# lora-slim.net
KiCad netlist of a schematic drawn in EAGLE
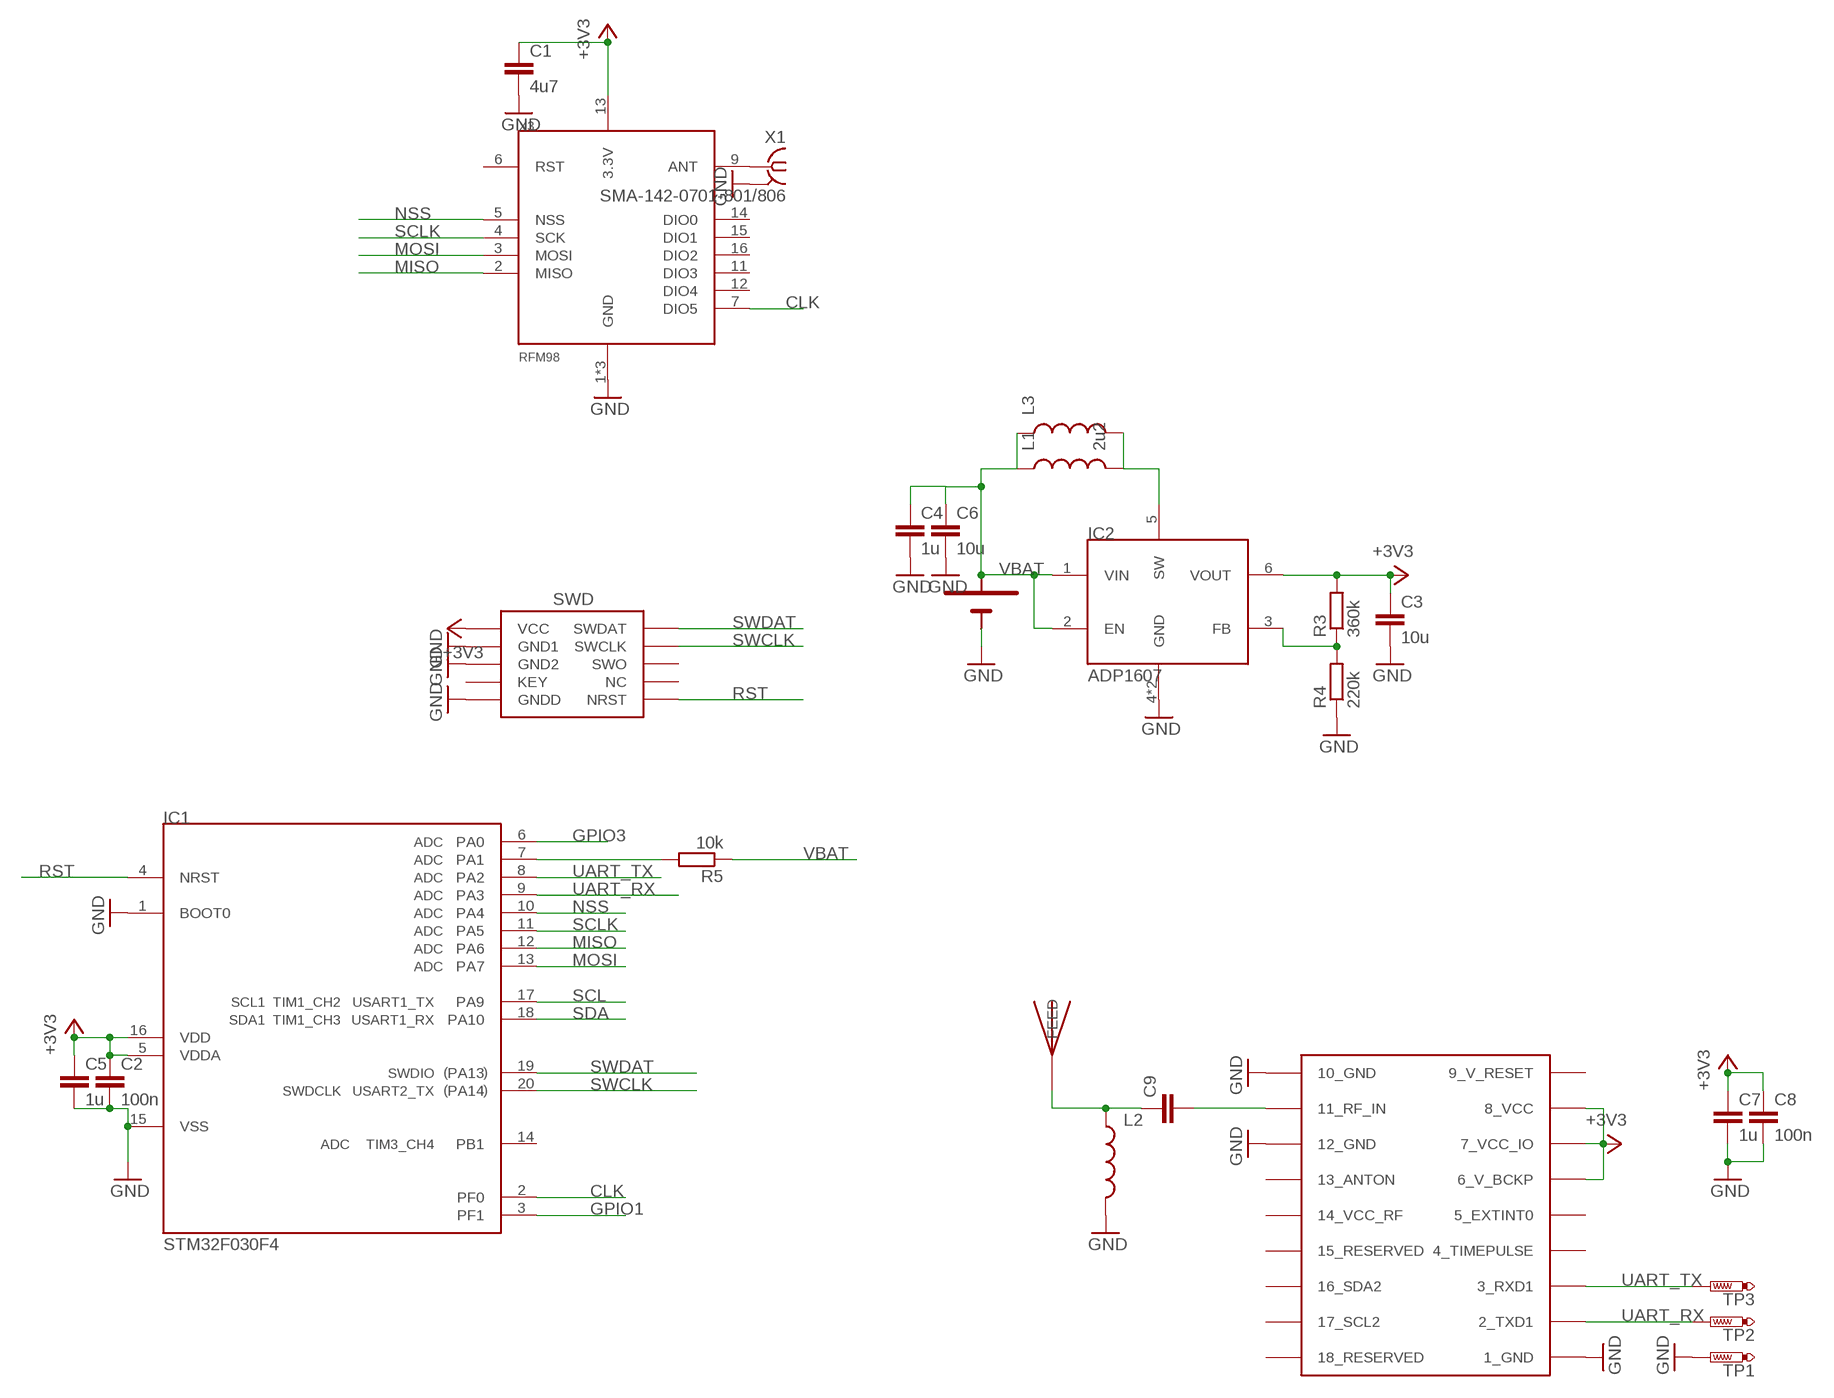
[diagram p0: schematic, sheet 1]

(export (version "E")
  (design (tool "Eeschema 10.0.6"))
  (components
    (comp (ref "C1")
      (value "4u7")
      (footprint "eagle-import:C0603")
      (libsource (lib "eagle-import") (part "C-EUC0603"))
    )
    (comp (ref "C2")
      (value "100n")
      (footprint "eagle-import:C0603")
      (libsource (lib "eagle-import") (part "C-EUC0603"))
    )
    (comp (ref "C3")
      (value "10u")
      (footprint "eagle-import:C0805")
      (libsource (lib "eagle-import") (part "C-EUC0805"))
    )
    (comp (ref "C4")
      (value "1u")
      (footprint "eagle-import:C0603")
      (libsource (lib "eagle-import") (part "C-EUC0603"))
    )
    (comp (ref "C5")
      (value "1u")
      (footprint "eagle-import:C0603")
      (libsource (lib "eagle-import") (part "C-EUC0603"))
    )
    (comp (ref "C6")
      (value "10u")
      (footprint "eagle-import:C0805")
      (libsource (lib "eagle-import") (part "C-EUC0805"))
    )
    (comp (ref "C7")
      (value "1u")
      (footprint "eagle-import:C0603")
      (libsource (lib "eagle-import") (part "C-EUC0603"))
    )
    (comp (ref "C8")
      (value "100n")
      (footprint "eagle-import:C0603")
      (libsource (lib "eagle-import") (part "C-EUC0603"))
    )
    (comp (ref "C9")
      (value "C-EUC0603")
      (footprint "eagle-import:C0603")
      (libsource (lib "eagle-import") (part "C-EUC0603"))
    )
    (comp (ref "IC1")
      (value "STM32F030F4")
      (footprint "eagle-import:TSSOP20")
      (libsource (lib "eagle-import") (part "STM32F030F4"))
    )
    (comp (ref "IC2")
      (value "ADP1607")
      (footprint "eagle-import:LFCSP6")
      (libsource (lib "eagle-import") (part "ADP1607"))
    )
    (comp (ref "J1")
      (value "SWD_PTH_SHROUD")
      (footprint "eagle-import:SWD_PTH_SHROUD")
      (libsource (lib "eagle-import") (part "SWD_PTH_SHROUD"))
    )
    (comp (ref "L1")
      (value "2u2")
      (footprint "eagle-import:0805")
      (libsource (lib "eagle-import") (part "INDUCTOR0805"))
    )
    (comp (ref "L2")
      (value "INDUCTOR0603")
      (footprint "eagle-import:0603")
      (libsource (lib "eagle-import") (part "INDUCTOR0603"))
    )
    (comp (ref "L3")
      (value "INDUCTOR1210")
      (footprint "eagle-import:1210")
      (libsource (lib "eagle-import") (part "INDUCTOR1210"))
    )
    (comp (ref "R3")
      (value "360k")
      (footprint "eagle-import:R0603")
      (libsource (lib "eagle-import") (part "R-EU_R0603"))
    )
    (comp (ref "R4")
      (value "220k")
      (footprint "eagle-import:R0603")
      (libsource (lib "eagle-import") (part "R-EU_R0603"))
    )
    (comp (ref "R5")
      (value "10k")
      (footprint "eagle-import:R0603")
      (libsource (lib "eagle-import") (part "R-EU_R0603"))
    )
    (comp (ref "TP1")
      (value "PTR1B1,27")
      (footprint "eagle-import:B1,27")
      (libsource (lib "eagle-import") (part "PTR1B1,27"))
    )
    (comp (ref "TP2")
      (value "PTR1B1,27")
      (footprint "eagle-import:B1,27")
      (libsource (lib "eagle-import") (part "PTR1B1,27"))
    )
    (comp (ref "TP3")
      (value "PTR1B1,27")
      (footprint "eagle-import:B1,27")
      (libsource (lib "eagle-import") (part "PTR1B1,27"))
    )
    (comp (ref "U$5")
      (value "JTI_ANTENNA-1575AT43A40")
      (footprint "eagle-import:JTI_ANTENNA-1575AT43A40")
      (libsource (lib "eagle-import") (part "JTI_ANTENNA-1575AT43A40"))
    )
    (comp (ref "U$6")
      (value "KEYSTONE-53")
      (footprint "eagle-import:KEYSTONE53")
      (libsource (lib "eagle-import") (part "KEYSTONE-53"))
    )
    (comp (ref "X1")
      (value "SMA-142-0701-801/806")
      (footprint "eagle-import:J502-ND-142-0701-801_806")
      (fields (field (name "MF") "JOHNSON COMPONENTS") (field (name "MPN") "142-0701-801"))
      (libsource (lib "eagle-import") (part "SMA-142-0701-801/806"))
    )
    (comp (ref "X2")
      (value "UBLOX_MAX")
      (footprint "eagle-import:UBLOX_MAX")
      (libsource (lib "eagle-import") (part "UBLOX_MAX"))
    )
    (comp (ref "X3")
      (value "RFM98")
      (footprint "eagle-import:RFM97")
      (libsource (lib "eagle-import") (part "RFM98"))
    )
  )
  (nets
    (net (code "1") (name "+3V3") (class "Default")
      (node (ref "C1") (pin "1") (pinfunction "1_1") (pintype "passive"))
      (node (ref "C2") (pin "1") (pinfunction "1_1") (pintype "passive"))
      (node (ref "C3") (pin "1") (pinfunction "1_1") (pintype "passive"))
      (node (ref "C5") (pin "1") (pinfunction "1_1") (pintype "passive"))
      (node (ref "C7") (pin "1") (pinfunction "1_1") (pintype "passive"))
      (node (ref "C8") (pin "1") (pinfunction "1_1") (pintype "passive"))
      (node (ref "IC1") (pin "16") (pinfunction "VDD_16") (pintype "power_in"))
      (node (ref "IC1") (pin "5") (pinfunction "VDDA_5") (pintype "power_in"))
      (node (ref "IC2") (pin "6") (pinfunction "VOUT_6") (pintype "output"))
      (node (ref "J1") (pin "1") (pinfunction "VCC_1") (pintype "power_in"))
      (node (ref "R3") (pin "2") (pinfunction "2_2") (pintype "passive"))
      (node (ref "X2") (pin "6_V_BCKP") (pinfunction "6_V_BCKP_6_V_BCKP") (pintype "bidirectional"))
      (node (ref "X2") (pin "7_VCC_IO") (pinfunction "7_VCC_IO_7_VCC_IO") (pintype "power_in"))
      (node (ref "X2") (pin "8_VCC") (pinfunction "8_VCC_8_VCC") (pintype "power_in"))
      (node (ref "X3") (pin "13") (pinfunction "3.3V_13") (pintype "power_in"))
    )
    (net (code "2") (name "/9_V_RESET") (class "Default")
      (node (ref "X2") (pin "9_V_RESET") (pinfunction "9_V_RESET_9_V_RESET") (pintype "power_in"))
    )
    (net (code "3") (name "/CLK") (class "Default")
      (node (ref "IC1") (pin "2") (pinfunction "PF0_2") (pintype "bidirectional"))
      (node (ref "X3") (pin "7") (pinfunction "DIO5_7") (pintype "bidirectional"))
    )
    (net (code "4") (name "/GPIO1") (class "Default")
      (node (ref "IC1") (pin "3") (pinfunction "PF1_3") (pintype "bidirectional"))
    )
    (net (code "5") (name "/GPIO3") (class "Default")
      (node (ref "IC1") (pin "6") (pinfunction "PA0_6") (pintype "bidirectional"))
    )
    (net (code "6") (name "/MISO") (class "Default")
      (node (ref "IC1") (pin "12") (pinfunction "PA6_12") (pintype "bidirectional"))
      (node (ref "X3") (pin "2") (pinfunction "MISO_2") (pintype "output"))
    )
    (net (code "7") (name "/MOSI") (class "Default")
      (node (ref "IC1") (pin "13") (pinfunction "PA7_13") (pintype "bidirectional"))
      (node (ref "X3") (pin "3") (pinfunction "MOSI_3") (pintype "input"))
    )
    (net (code "8") (name "/NSS") (class "Default")
      (node (ref "IC1") (pin "10") (pinfunction "PA4_10") (pintype "bidirectional"))
      (node (ref "X3") (pin "5") (pinfunction "NSS_5") (pintype "input"))
    )
    (net (code "9") (name "/RST") (class "Default")
      (node (ref "IC1") (pin "4") (pinfunction "NRST_4") (pintype "input"))
      (node (ref "J1") (pin "10") (pinfunction "NRST_10") (pintype "bidirectional"))
    )
    (net (code "10") (name "/SCL") (class "Default")
      (node (ref "IC1") (pin "17") (pinfunction "PA9_17") (pintype "bidirectional"))
    )
    (net (code "11") (name "/SCLK") (class "Default")
      (node (ref "IC1") (pin "11") (pinfunction "PA5_11") (pintype "bidirectional"))
      (node (ref "X3") (pin "4") (pinfunction "SCK_4") (pintype "input"))
    )
    (net (code "12") (name "/SDA") (class "Default")
      (node (ref "IC1") (pin "18") (pinfunction "PA10_18") (pintype "bidirectional"))
    )
    (net (code "13") (name "/SWCLK") (class "Default")
      (node (ref "IC1") (pin "20") (pinfunction "PA14_20") (pintype "bidirectional"))
      (node (ref "J1") (pin "4") (pinfunction "SWCLK_4") (pintype "bidirectional"))
    )
    (net (code "14") (name "/SWDAT") (class "Default")
      (node (ref "IC1") (pin "19") (pinfunction "PA13_19") (pintype "bidirectional"))
      (node (ref "J1") (pin "2") (pinfunction "SWDAT_2") (pintype "bidirectional"))
    )
    (net (code "15") (name "/UART_RX") (class "Default")
      (node (ref "IC1") (pin "9") (pinfunction "PA3_9") (pintype "bidirectional"))
      (node (ref "TP2") (pin "TP") (pinfunction "TP_TP") (pintype "input"))
      (node (ref "X2") (pin "2_TXD1") (pinfunction "2_TXD1_2_TXD1") (pintype "bidirectional"))
    )
    (net (code "16") (name "/UART_TX") (class "Default")
      (node (ref "IC1") (pin "8") (pinfunction "PA2_8") (pintype "bidirectional"))
      (node (ref "TP3") (pin "TP") (pinfunction "TP_TP") (pintype "input"))
      (node (ref "X2") (pin "3_RXD1") (pinfunction "3_RXD1_3_RXD1") (pintype "bidirectional"))
    )
    (net (code "17") (name "/VBAT") (class "Default")
      (node (ref "C4") (pin "1") (pinfunction "1_1") (pintype "passive"))
      (node (ref "C6") (pin "1") (pinfunction "1_1") (pintype "passive"))
      (node (ref "IC2") (pin "1") (pinfunction "VIN_1") (pintype "input"))
      (node (ref "IC2") (pin "2") (pinfunction "EN_2") (pintype "input"))
      (node (ref "L1") (pin "1") (pinfunction "1_1") (pintype "passive"))
      (node (ref "L3") (pin "1") (pinfunction "1_1") (pintype "passive"))
      (node (ref "R5") (pin "1") (pinfunction "1_1") (pintype "passive"))
      (node (ref "U$6") (pin "P1") (pinfunction "+_P1") (pintype "passive"))
      (node (ref "U$6") (pin "P2") (pinfunction "+_P2") (pintype "passive"))
    )
    (net (code "18") (name "GND") (class "Default")
      (node (ref "C1") (pin "2") (pinfunction "2_2") (pintype "passive"))
      (node (ref "C2") (pin "2") (pinfunction "2_2") (pintype "passive"))
      (node (ref "C3") (pin "2") (pinfunction "2_2") (pintype "passive"))
      (node (ref "C4") (pin "2") (pinfunction "2_2") (pintype "passive"))
      (node (ref "C5") (pin "2") (pinfunction "2_2") (pintype "passive"))
      (node (ref "C6") (pin "2") (pinfunction "2_2") (pintype "passive"))
      (node (ref "C7") (pin "2") (pinfunction "2_2") (pintype "passive"))
      (node (ref "C8") (pin "2") (pinfunction "2_2") (pintype "passive"))
      (node (ref "IC1") (pin "1") (pinfunction "BOOT0_1") (pintype "input"))
      (node (ref "IC1") (pin "15") (pinfunction "VSS_15") (pintype "power_in"))
      (node (ref "IC2") (pin "4") (pinfunction "GND_4") (pintype "power_in"))
      (node (ref "IC2") (pin "EP") (pinfunction "GND_EP") (pintype "power_in"))
      (node (ref "J1") (pin "3") (pinfunction "GND1_3") (pintype "power_in"))
      (node (ref "J1") (pin "5") (pinfunction "GND2_5") (pintype "power_in"))
      (node (ref "J1") (pin "9") (pinfunction "GNDD_9") (pintype "power_in"))
      (node (ref "L2") (pin "2") (pinfunction "2_2") (pintype "passive"))
      (node (ref "R4") (pin "1") (pinfunction "1_1") (pintype "passive"))
      (node (ref "TP1") (pin "TP") (pinfunction "TP_TP") (pintype "input"))
      (node (ref "U$6") (pin "N1") (pinfunction "-_N1") (pintype "passive"))
      (node (ref "U$6") (pin "N2") (pinfunction "-_N2") (pintype "passive"))
      (node (ref "X1") (pin "G@1") (pinfunction "2_G@1") (pintype "passive"))
      (node (ref "X1") (pin "G@2") (pinfunction "2_G@2") (pintype "passive"))
      (node (ref "X1") (pin "G@3") (pinfunction "2_G@3") (pintype "passive"))
      (node (ref "X1") (pin "G@4") (pinfunction "2_G@4") (pintype "passive"))
      (node (ref "X2") (pin "10_GND") (pinfunction "10_GND_10_GND") (pintype "power_in"))
      (node (ref "X2") (pin "12_GND") (pinfunction "12_GND_12_GND") (pintype "power_in"))
      (node (ref "X2") (pin "1_GND") (pinfunction "1_GND_1_GND") (pintype "power_in"))
      (node (ref "X3") (pin "1") (pinfunction "GND_1") (pintype "power_in"))
      (node (ref "X3") (pin "10") (pinfunction "GND_10") (pintype "power_in"))
      (node (ref "X3") (pin "8") (pinfunction "GND_8") (pintype "power_in"))
    )
    (net (code "19") (name "Net-(C9-Pad1)") (class "Default")
      (node (ref "C9") (pin "1") (pinfunction "1_1") (pintype "passive"))
      (node (ref "L2") (pin "1") (pinfunction "1_1") (pintype "passive"))
      (node (ref "U$5") (pin "FEED") (pinfunction "FEED_FEED") (pintype "bidirectional"))
    )
    (net (code "20") (name "Net-(C9-Pad2)") (class "Default")
      (node (ref "C9") (pin "2") (pinfunction "2_2") (pintype "passive"))
      (node (ref "X2") (pin "11_RF_IN") (pinfunction "11_RF_IN_11_RF_IN") (pintype "bidirectional"))
    )
    (net (code "21") (name "Net-(IC1-PA1)") (class "Default")
      (node (ref "IC1") (pin "7") (pinfunction "PA1_7") (pintype "bidirectional"))
      (node (ref "R5") (pin "2") (pinfunction "2_2") (pintype "passive"))
    )
    (net (code "22") (name "Net-(IC2-FB)") (class "Default")
      (node (ref "IC2") (pin "3") (pinfunction "FB_3") (pintype "input"))
      (node (ref "R3") (pin "1") (pinfunction "1_1") (pintype "passive"))
      (node (ref "R4") (pin "2") (pinfunction "2_2") (pintype "passive"))
    )
    (net (code "23") (name "Net-(IC2-SW)") (class "Default")
      (node (ref "IC2") (pin "5") (pinfunction "SW_5") (pintype "input"))
      (node (ref "L1") (pin "2") (pinfunction "2_2") (pintype "passive"))
      (node (ref "L3") (pin "2") (pinfunction "2_2") (pintype "passive"))
    )
    (net (code "24") (name "Net-(X3-ANT)") (class "Default")
      (node (ref "X1") (pin "1") (pinfunction "1_1") (pintype "passive"))
      (node (ref "X3") (pin "9") (pinfunction "ANT_9") (pintype "bidirectional"))
    )
    (net (code "25") (name "unconnected-(IC1-PB1-Pad14)") (class "Default")
      (node (ref "IC1") (pin "14") (pinfunction "PB1_14") (pintype "bidirectional"))
    )
    (net (code "26") (name "unconnected-(J1-KEY-Pad7)") (class "Default")
      (node (ref "J1") (pin "7") (pinfunction "KEY_7") (pintype "bidirectional"))
    )
    (net (code "27") (name "unconnected-(J1-NC-Pad8)") (class "Default")
      (node (ref "J1") (pin "8") (pinfunction "NC_8") (pintype "no_connect"))
    )
    (net (code "28") (name "unconnected-(J1-SWO-Pad6)") (class "Default")
      (node (ref "J1") (pin "6") (pinfunction "SWO_6") (pintype "bidirectional"))
    )
    (net (code "29") (name "unconnected-(X2-Pad4_TIMEPULSE)") (class "Default")
      (node (ref "X2") (pin "4_TIMEPULSE") (pinfunction "4_TIMEPULSE_4_TIMEPULSE") (pintype "bidirectional"))
    )
    (net (code "30") (name "unconnected-(X2-Pad5_EXTINT0)") (class "Default")
      (node (ref "X2") (pin "5_EXTINT0") (pinfunction "5_EXTINT0_5_EXTINT0") (pintype "bidirectional"))
    )
    (net (code "31") (name "unconnected-(X2-Pad13_ANTON)") (class "Default")
      (node (ref "X2") (pin "13_ANTON") (pinfunction "13_ANTON_13_ANTON") (pintype "bidirectional"))
    )
    (net (code "32") (name "unconnected-(X2-Pad14_VCC_RF)") (class "Default")
      (node (ref "X2") (pin "14_VCC_RF") (pinfunction "14_VCC_RF_14_VCC_RF") (pintype "bidirectional"))
    )
    (net (code "33") (name "unconnected-(X2-Pad15_RESERVED)") (class "Default")
      (node (ref "X2") (pin "15_RESERVED") (pinfunction "15_RESERVED_15_RESERVED") (pintype "bidirectional"))
    )
    (net (code "34") (name "unconnected-(X2-Pad16_SDA2)") (class "Default")
      (node (ref "X2") (pin "16_SDA2") (pinfunction "16_SDA2_16_SDA2") (pintype "bidirectional"))
    )
    (net (code "35") (name "unconnected-(X2-Pad17_SCL2)") (class "Default")
      (node (ref "X2") (pin "17_SCL2") (pinfunction "17_SCL2_17_SCL2") (pintype "bidirectional"))
    )
    (net (code "36") (name "unconnected-(X2-Pad18_RESERVED)") (class "Default")
      (node (ref "X2") (pin "18_RESERVED") (pinfunction "18_RESERVED_18_RESERVED") (pintype "bidirectional"))
    )
    (net (code "37") (name "unconnected-(X3-DIO0-Pad14)") (class "Default")
      (node (ref "X3") (pin "14") (pinfunction "DIO0_14") (pintype "bidirectional"))
    )
    (net (code "38") (name "unconnected-(X3-DIO1-Pad15)") (class "Default")
      (node (ref "X3") (pin "15") (pinfunction "DIO1_15") (pintype "bidirectional"))
    )
    (net (code "39") (name "unconnected-(X3-DIO2-Pad16)") (class "Default")
      (node (ref "X3") (pin "16") (pinfunction "DIO2_16") (pintype "bidirectional"))
    )
    (net (code "40") (name "unconnected-(X3-DIO3-Pad11)") (class "Default")
      (node (ref "X3") (pin "11") (pinfunction "DIO3_11") (pintype "bidirectional"))
    )
    (net (code "41") (name "unconnected-(X3-DIO4-Pad12)") (class "Default")
      (node (ref "X3") (pin "12") (pinfunction "DIO4_12") (pintype "bidirectional"))
    )
    (net (code "42") (name "unconnected-(X3-RST-Pad6)") (class "Default")
      (node (ref "X3") (pin "6") (pinfunction "RST_6") (pintype "input"))
    )
  )
)
